# simulation_json.net
KiCad netlist of a schematic drawn in EasyEDA
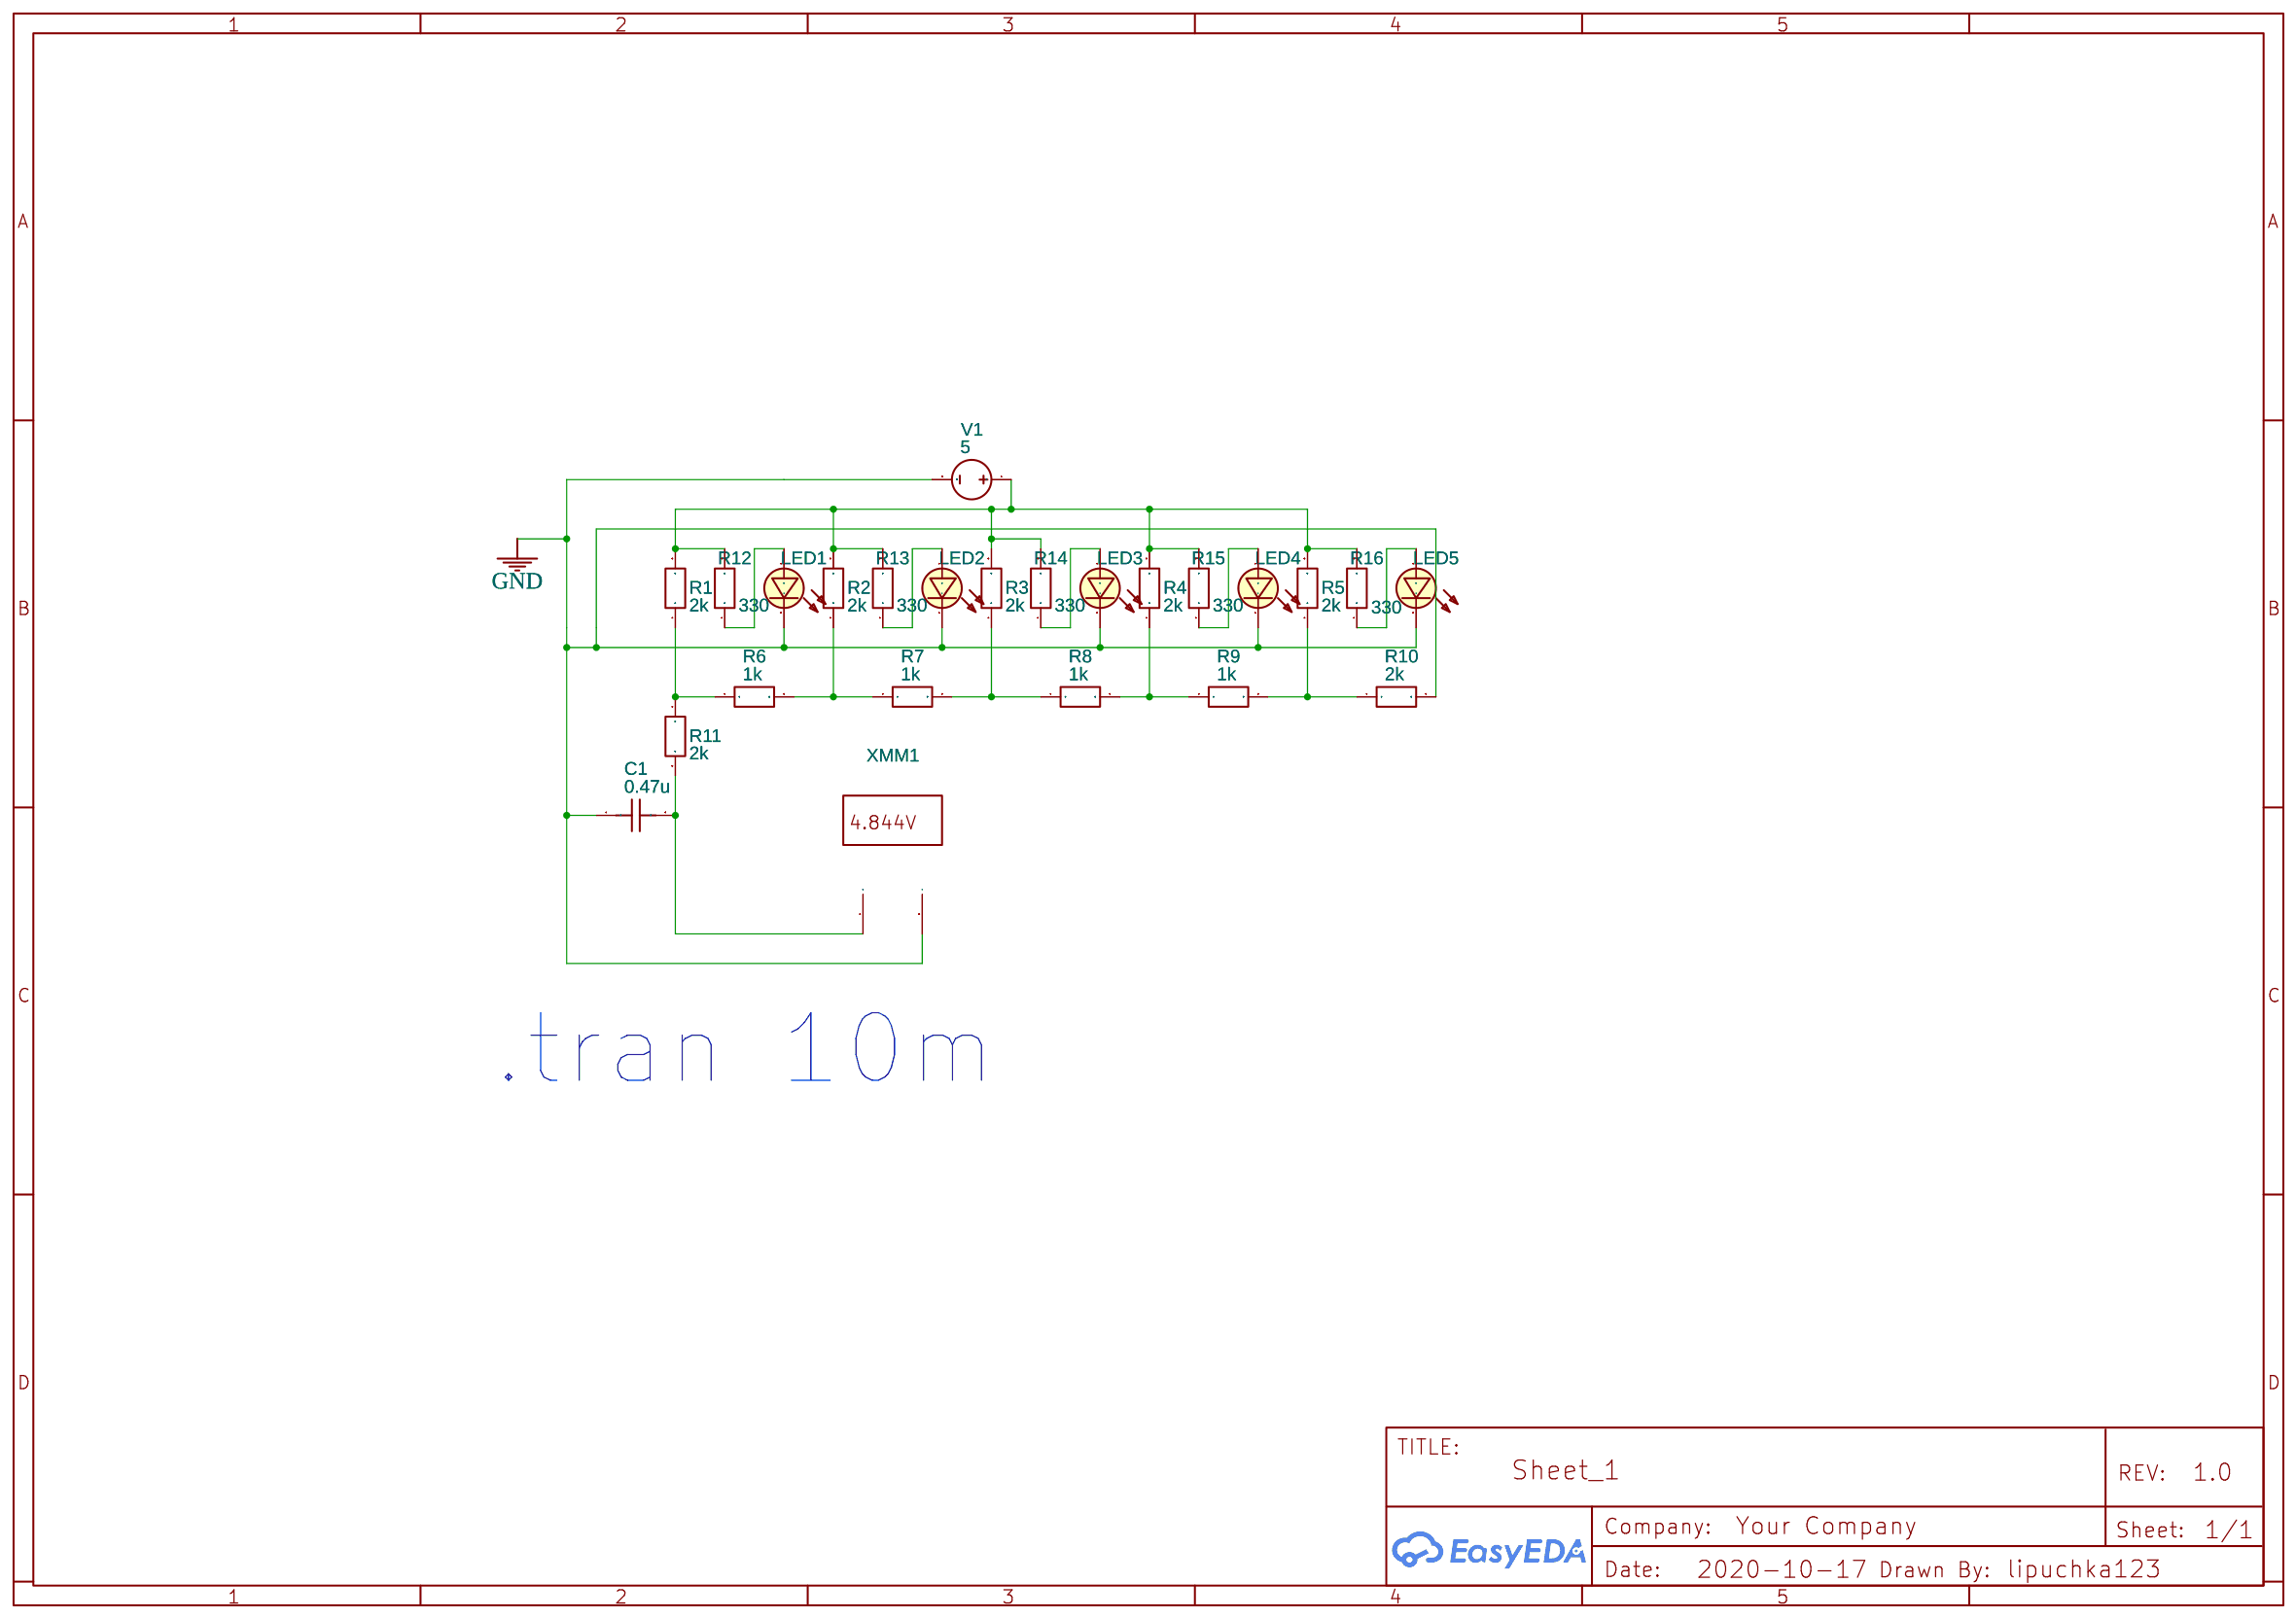
[diagram p0: schematic sheet]

(export (version "E")
  (design (tool "Eeschema 10.0.6"))
  (components
    (comp (ref "C1") (value "0.47u") (libsource (lib "") (part "C_0603_US")))
    (comp (ref "LED1") (value "LED") (libsource (lib "") (part "LED")))
    (comp (ref "LED2") (value "LED") (libsource (lib "") (part "LED")))
    (comp (ref "LED3") (value "LED") (libsource (lib "") (part "LED")))
    (comp (ref "LED4") (value "LED") (libsource (lib "") (part "LED")))
    (comp (ref "LED5") (value "LED") (libsource (lib "") (part "LED")))
    (comp (ref "R1") (value "2k") (libsource (lib "") (part "R_0402_EU")))
    (comp (ref "R2") (value "2k") (libsource (lib "") (part "R_0402_EU")))
    (comp (ref "R3") (value "2k") (libsource (lib "") (part "R_0402_EU")))
    (comp (ref "R4") (value "2k") (libsource (lib "") (part "R_0402_EU")))
    (comp (ref "R5") (value "2k") (libsource (lib "") (part "R_0402_EU")))
    (comp (ref "R6") (value "1k") (libsource (lib "") (part "R_0402_EU_1")))
    (comp (ref "R7") (value "1k") (libsource (lib "") (part "R_0402_EU_1")))
    (comp (ref "R8") (value "1k") (libsource (lib "") (part "R_0402_EU_1")))
    (comp (ref "R9") (value "1k") (libsource (lib "") (part "R_0402_EU_1")))
    (comp (ref "R10") (value "2k") (libsource (lib "") (part "R_0402_EU_1")))
    (comp (ref "R11") (value "2k") (libsource (lib "") (part "R_0402_EU_2")))
    (comp (ref "R12") (value "330") (libsource (lib "") (part "R_0402_EU")))
    (comp (ref "R13") (value "330") (libsource (lib "") (part "R_0402_EU")))
    (comp (ref "R14") (value "330") (libsource (lib "") (part "R_0402_EU")))
    (comp (ref "R15") (value "330") (libsource (lib "") (part "R_0402_EU")))
    (comp (ref "R16") (value "330") (libsource (lib "") (part "R_0402_EU")))
    (comp (ref "V1") (value "5") (libsource (lib "") (part "VDC")))
    (comp (ref "XMM1") (value "Multimeter") (libsource (lib "") (part "MULTIMETER")))
  )
  (nets
    (net (code "1") (name "GND") (class "Default")
      (node (ref "C1") (pin "1") (pinfunction "1_1") (pintype "unspecified"))
      (node (ref "LED1") (pin "2") (pinfunction "-_2") (pintype "unspecified"))
      (node (ref "LED2") (pin "2") (pinfunction "-_2") (pintype "unspecified"))
      (node (ref "LED3") (pin "2") (pinfunction "-_2") (pintype "unspecified"))
      (node (ref "LED4") (pin "2") (pinfunction "-_2") (pintype "unspecified"))
      (node (ref "LED5") (pin "2") (pinfunction "-_2") (pintype "unspecified"))
      (node (ref "R10") (pin "2") (pinfunction "2_2") (pintype "unspecified"))
      (node (ref "V1") (pin "2") (pinfunction "2_2") (pintype "unspecified"))
      (node (ref "XMM1") (pin "2") (pinfunction "I_2") (pintype "unspecified"))
    )
    (net (code "2") (name "Net-(LED1-+)") (class "Default")
      (node (ref "LED1") (pin "1") (pinfunction "+_1") (pintype "unspecified"))
      (node (ref "R12") (pin "1") (pinfunction "1_1") (pintype "unspecified"))
    )
    (net (code "3") (name "Net-(LED2-+)") (class "Default")
      (node (ref "LED2") (pin "1") (pinfunction "+_1") (pintype "unspecified"))
      (node (ref "R13") (pin "1") (pinfunction "1_1") (pintype "unspecified"))
    )
    (net (code "4") (name "Net-(LED3-+)") (class "Default")
      (node (ref "LED3") (pin "1") (pinfunction "+_1") (pintype "unspecified"))
      (node (ref "R14") (pin "1") (pinfunction "1_1") (pintype "unspecified"))
    )
    (net (code "5") (name "Net-(LED4-+)") (class "Default")
      (node (ref "LED4") (pin "1") (pinfunction "+_1") (pintype "unspecified"))
      (node (ref "R15") (pin "1") (pinfunction "1_1") (pintype "unspecified"))
    )
    (net (code "6") (name "Net-(LED5-+)") (class "Default")
      (node (ref "LED5") (pin "1") (pinfunction "+_1") (pintype "unspecified"))
      (node (ref "R16") (pin "1") (pinfunction "1_1") (pintype "unspecified"))
    )
    (net (code "7") (name "Net-(R1-Pad1)") (class "Default")
      (node (ref "R1") (pin "1") (pinfunction "1_1") (pintype "unspecified"))
      (node (ref "R11") (pin "1") (pinfunction "1_1") (pintype "unspecified"))
      (node (ref "R6") (pin "1") (pinfunction "1_1") (pintype "unspecified"))
    )
    (net (code "8") (name "Net-(R1-Pad2)") (class "Default")
      (node (ref "R1") (pin "2") (pinfunction "2_2") (pintype "unspecified"))
      (node (ref "R12") (pin "2") (pinfunction "2_2") (pintype "unspecified"))
      (node (ref "R13") (pin "2") (pinfunction "2_2") (pintype "unspecified"))
      (node (ref "R14") (pin "2") (pinfunction "2_2") (pintype "unspecified"))
      (node (ref "R15") (pin "2") (pinfunction "2_2") (pintype "unspecified"))
      (node (ref "R16") (pin "2") (pinfunction "2_2") (pintype "unspecified"))
      (node (ref "R2") (pin "2") (pinfunction "2_2") (pintype "unspecified"))
      (node (ref "R3") (pin "2") (pinfunction "2_2") (pintype "unspecified"))
      (node (ref "R4") (pin "2") (pinfunction "2_2") (pintype "unspecified"))
      (node (ref "R5") (pin "2") (pinfunction "2_2") (pintype "unspecified"))
      (node (ref "V1") (pin "1") (pinfunction "1_1") (pintype "unspecified"))
    )
    (net (code "9") (name "Net-(R2-Pad1)") (class "Default")
      (node (ref "R2") (pin "1") (pinfunction "1_1") (pintype "unspecified"))
      (node (ref "R6") (pin "2") (pinfunction "2_2") (pintype "unspecified"))
      (node (ref "R7") (pin "1") (pinfunction "1_1") (pintype "unspecified"))
    )
    (net (code "10") (name "Net-(R3-Pad1)") (class "Default")
      (node (ref "R3") (pin "1") (pinfunction "1_1") (pintype "unspecified"))
      (node (ref "R7") (pin "2") (pinfunction "2_2") (pintype "unspecified"))
      (node (ref "R8") (pin "1") (pinfunction "1_1") (pintype "unspecified"))
    )
    (net (code "11") (name "Net-(R4-Pad1)") (class "Default")
      (node (ref "R4") (pin "1") (pinfunction "1_1") (pintype "unspecified"))
      (node (ref "R8") (pin "2") (pinfunction "2_2") (pintype "unspecified"))
      (node (ref "R9") (pin "1") (pinfunction "1_1") (pintype "unspecified"))
    )
    (net (code "12") (name "Net-(R10-Pad1)") (class "Default")
      (node (ref "R10") (pin "1") (pinfunction "1_1") (pintype "unspecified"))
      (node (ref "R5") (pin "1") (pinfunction "1_1") (pintype "unspecified"))
      (node (ref "R9") (pin "2") (pinfunction "2_2") (pintype "unspecified"))
    )
    (net (code "13") (name "Net-(XMM1-+)") (class "Default")
      (node (ref "C1") (pin "2") (pinfunction "2_2") (pintype "unspecified"))
      (node (ref "R11") (pin "2") (pinfunction "2_2") (pintype "unspecified"))
      (node (ref "XMM1") (pin "1") (pinfunction "+_1") (pintype "unspecified"))
    )
  )
)
